# bristol_longshot.net
KiCad netlist of a schematic drawn in EAGLE
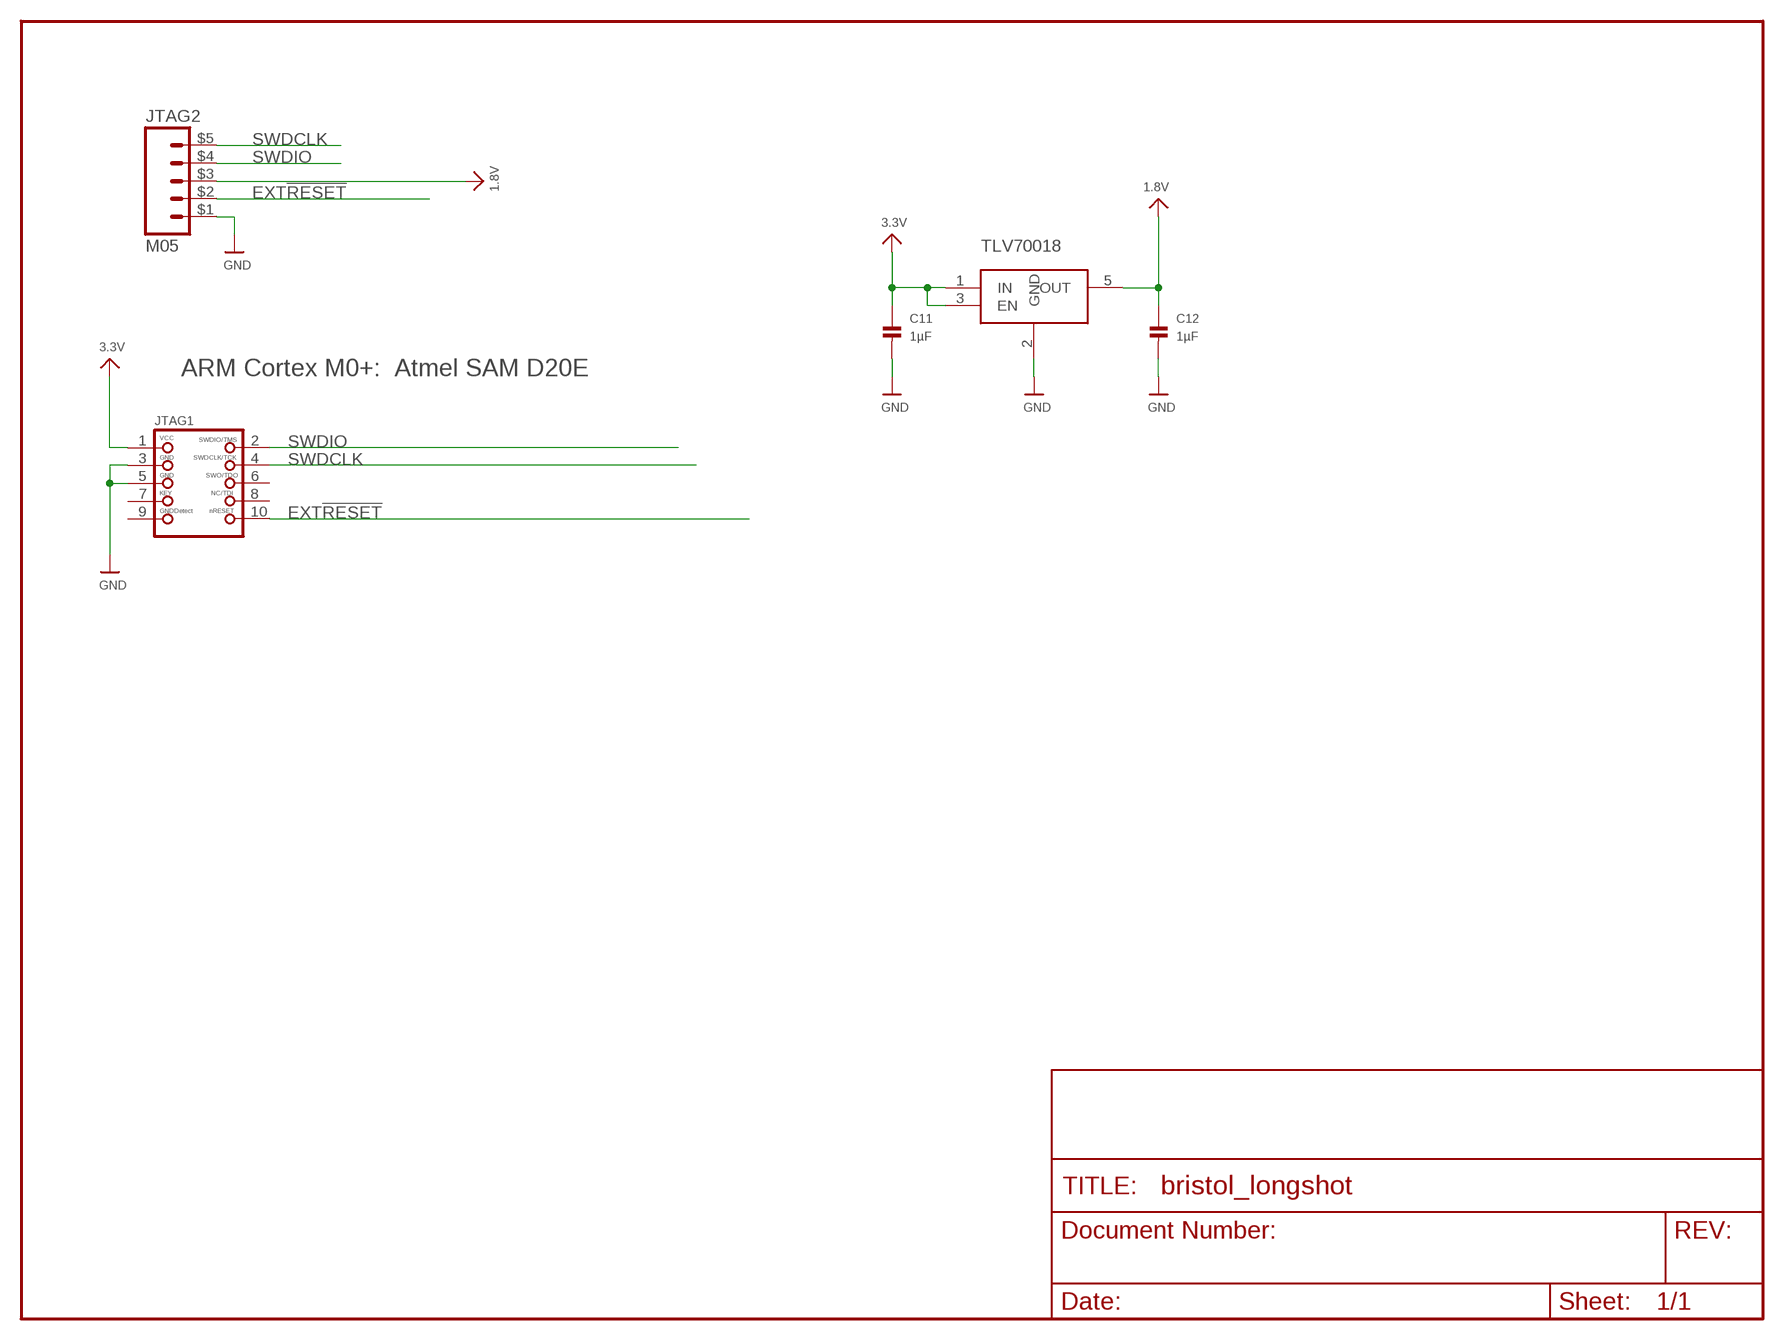
[diagram p0: schematic, sheet 1]

(export (version "E")
  (design (tool "Eeschema 10.0.6"))
  (components
    (comp (ref "C11")
      (value "1µF")
      (footprint "eagle-import:_0402")
      (libsource (lib "eagle-import") (part "CAP_CERAMIC_0402"))
    )
    (comp (ref "C12")
      (value "1µF")
      (footprint "eagle-import:_0402")
      (libsource (lib "eagle-import") (part "CAP_CERAMIC_0402"))
    )
    (comp (ref "JTAG1")
      (value "JTAG-CORTEXM3SMT")
      (footprint "eagle-import:2X05_1.27MM_SMT")
      (libsource (lib "eagle-import") (part "JTAG-CORTEXM3SMT"))
    )
    (comp (ref "JTAG2")
      (value "M05")
      (footprint "eagle-import:M05_SIDE")
      (libsource (lib "eagle-import") (part "M05"))
    )
    (comp (ref "U1")
      (value "TLV70018DCK")
      (footprint "eagle-import:SC70-5L")
      (libsource (lib "eagle-import") (part "TLV700DCK"))
    )
  )
  (nets
    (net (code "1") (name "/EXT~{RESET}") (class "Default")
      (node (ref "JTAG1") (pin "10") (pinfunction "10_10") (pintype "passive"))
      (node (ref "JTAG2") (pin "$2") (pinfunction "2_$2") (pintype "passive"))
    )
    (net (code "2") (name "/SWDCLK") (class "Default")
      (node (ref "JTAG1") (pin "4") (pinfunction "4_4") (pintype "passive"))
      (node (ref "JTAG2") (pin "$5") (pinfunction "5_$5") (pintype "passive"))
    )
    (net (code "3") (name "/SWDIO") (class "Default")
      (node (ref "JTAG1") (pin "2") (pinfunction "2_2") (pintype "passive"))
      (node (ref "JTAG2") (pin "$4") (pinfunction "4_$4") (pintype "passive"))
    )
    (net (code "4") (name "1.8V") (class "Default")
      (node (ref "C12") (pin "1") (pinfunction "P$1_1") (pintype "passive"))
      (node (ref "JTAG2") (pin "$3") (pinfunction "3_$3") (pintype "passive"))
      (node (ref "U1") (pin "5") (pinfunction "OUT_5") (pintype "bidirectional"))
    )
    (net (code "5") (name "3.3V") (class "Default")
      (node (ref "C11") (pin "1") (pinfunction "P$1_1") (pintype "passive"))
      (node (ref "JTAG1") (pin "1") (pinfunction "1_1") (pintype "passive"))
      (node (ref "U1") (pin "1") (pinfunction "IN_1") (pintype "bidirectional"))
      (node (ref "U1") (pin "3") (pinfunction "EN_3") (pintype "bidirectional"))
    )
    (net (code "6") (name "GND") (class "Default")
      (node (ref "C11") (pin "2") (pinfunction "P$2_2") (pintype "passive"))
      (node (ref "C12") (pin "2") (pinfunction "P$2_2") (pintype "passive"))
      (node (ref "JTAG1") (pin "3") (pinfunction "3_3") (pintype "passive"))
      (node (ref "JTAG1") (pin "5") (pinfunction "5_5") (pintype "passive"))
      (node (ref "JTAG2") (pin "$1") (pinfunction "1_$1") (pintype "passive"))
      (node (ref "U1") (pin "2") (pinfunction "GND_2") (pintype "bidirectional"))
    )
    (net (code "7") (name "unconnected-(JTAG1-Pad6)") (class "Default")
      (node (ref "JTAG1") (pin "6") (pinfunction "6_6") (pintype "passive"))
    )
    (net (code "8") (name "unconnected-(JTAG1-Pad7)") (class "Default")
      (node (ref "JTAG1") (pin "7") (pinfunction "7_7") (pintype "passive"))
    )
    (net (code "9") (name "unconnected-(JTAG1-Pad8)") (class "Default")
      (node (ref "JTAG1") (pin "8") (pinfunction "8_8") (pintype "passive"))
    )
    (net (code "10") (name "unconnected-(JTAG1-Pad9)") (class "Default")
      (node (ref "JTAG1") (pin "9") (pinfunction "9_9") (pintype "passive"))
    )
  )
)
